# vswr.net
KiCad netlist of a schematic drawn in EAGLE
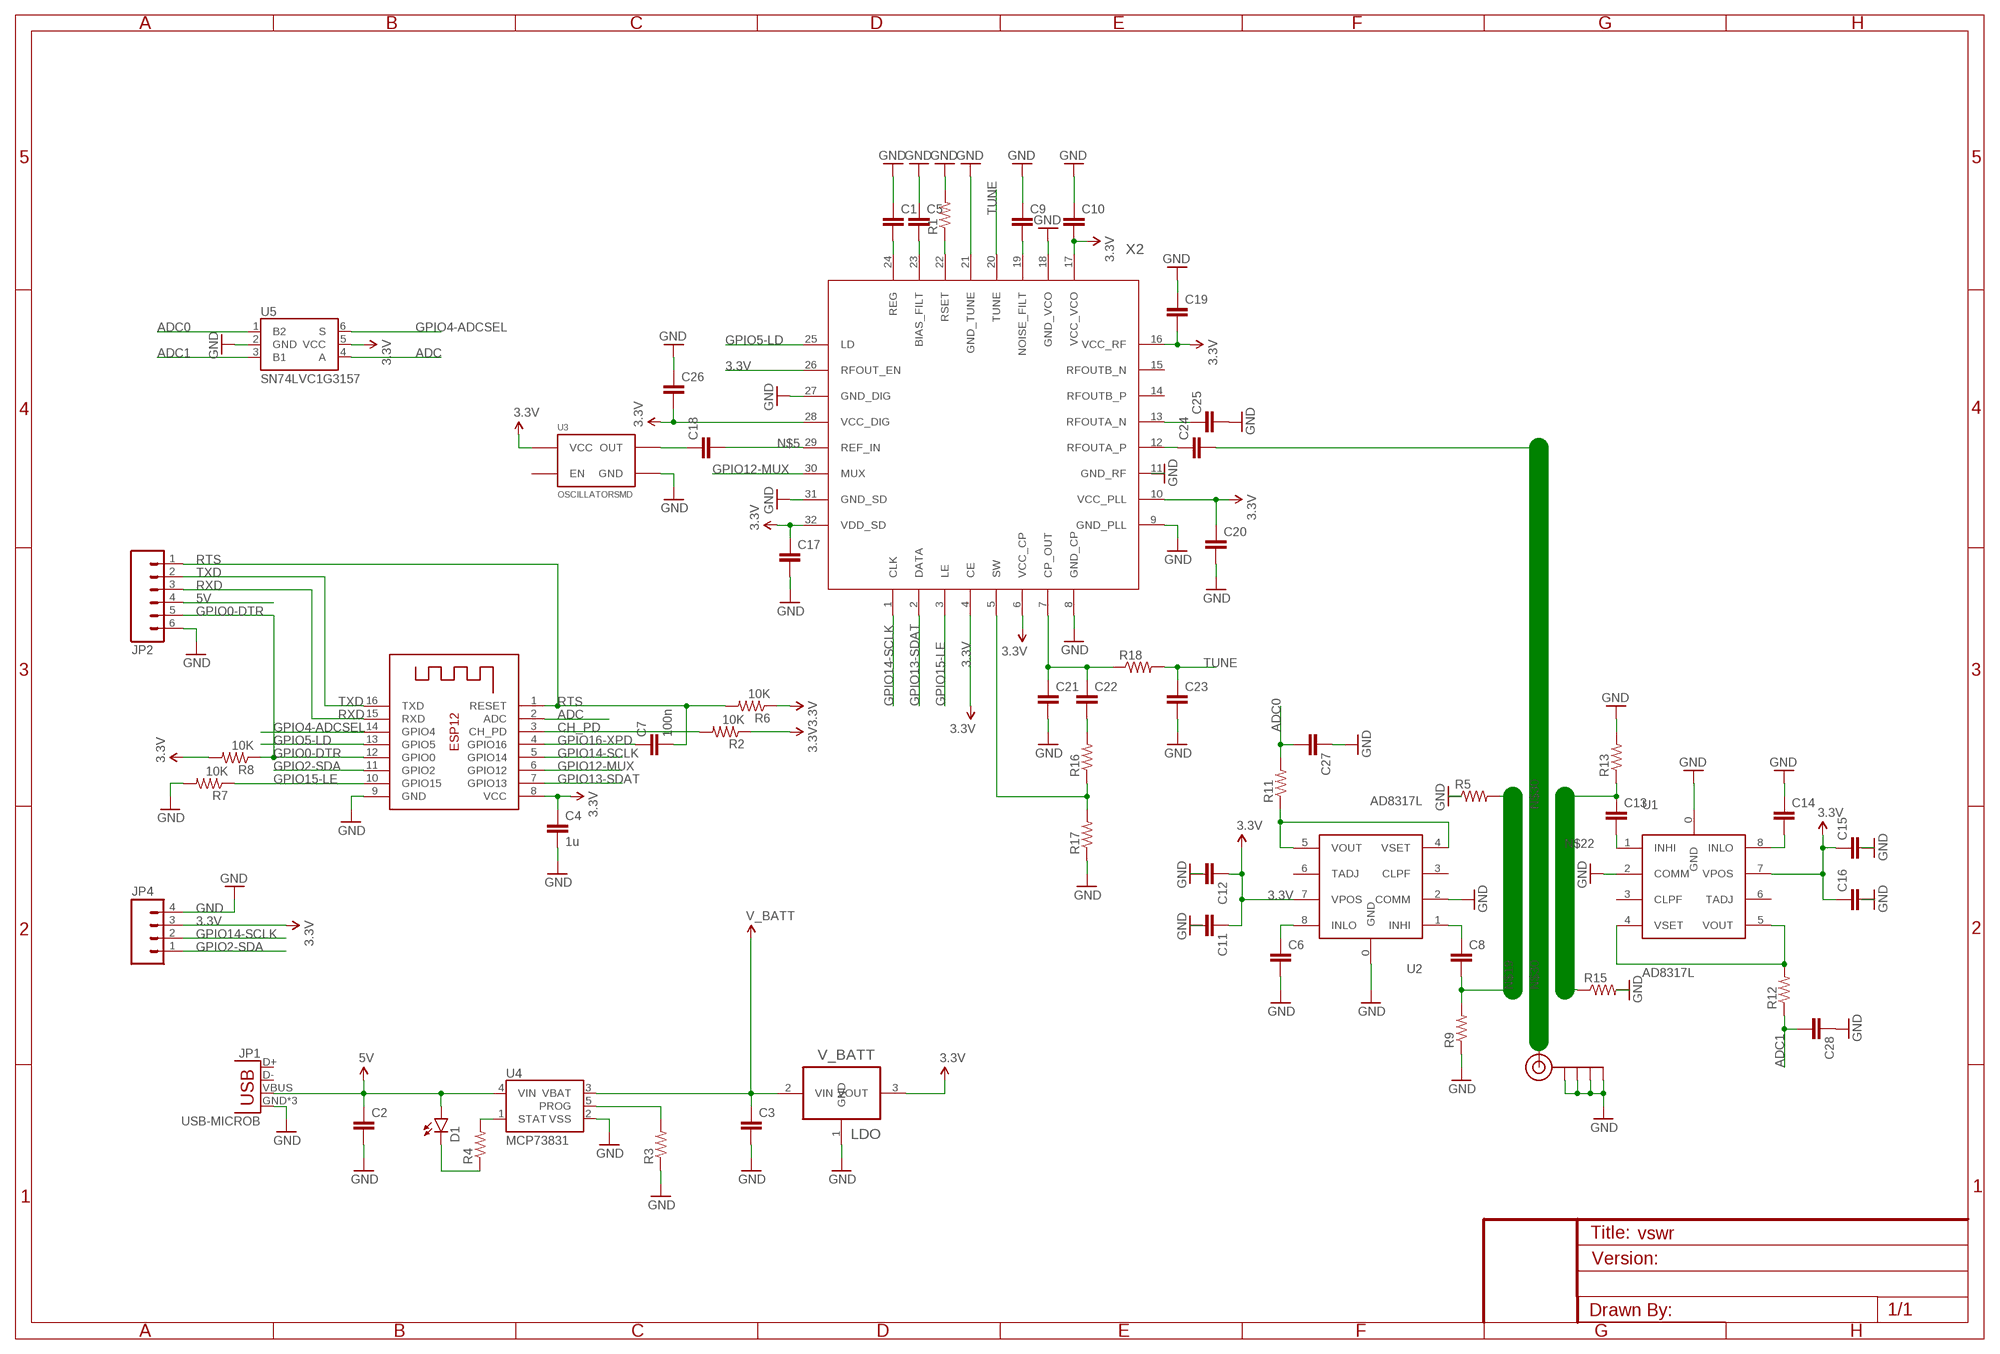
[diagram p0: schematic, sheet 1]

(export (version "E")
  (design (tool "Eeschema 10.0.6"))
  (components
    (comp (ref "C1")
      (value "CAP0402")
      (footprint "eagle-import:0402")
      (libsource (lib "eagle-import") (part "CAP0402"))
    )
    (comp (ref "C2")
      (value "CAP0603")
      (footprint "eagle-import:0603")
      (libsource (lib "eagle-import") (part "CAP0603"))
    )
    (comp (ref "C3")
      (value "CAP0603")
      (footprint "eagle-import:0603")
      (libsource (lib "eagle-import") (part "CAP0603"))
    )
    (comp (ref "C4")
      (value "1u")
      (footprint "eagle-import:0603")
      (libsource (lib "eagle-import") (part "naut_CAP0603"))
    )
    (comp (ref "C5")
      (value "CAP0402")
      (footprint "eagle-import:0402")
      (libsource (lib "eagle-import") (part "CAP0402"))
    )
    (comp (ref "C6")
      (value "CAP0402")
      (footprint "eagle-import:0402")
      (libsource (lib "eagle-import") (part "CAP0402"))
    )
    (comp (ref "C7")
      (value "100n")
      (footprint "eagle-import:0603")
      (libsource (lib "eagle-import") (part "naut_CAP0603"))
    )
    (comp (ref "C8")
      (value "CAP0402")
      (footprint "eagle-import:0402")
      (libsource (lib "eagle-import") (part "CAP0402"))
    )
    (comp (ref "C9")
      (value "CAP0402")
      (footprint "eagle-import:0402")
      (libsource (lib "eagle-import") (part "CAP0402"))
    )
    (comp (ref "C10")
      (value "CAP0402")
      (footprint "eagle-import:0402")
      (libsource (lib "eagle-import") (part "CAP0402"))
    )
    (comp (ref "C11")
      (value "CAP0402")
      (footprint "eagle-import:0402")
      (libsource (lib "eagle-import") (part "CAP0402"))
    )
    (comp (ref "C12")
      (value "CAP0603")
      (footprint "eagle-import:0603")
      (libsource (lib "eagle-import") (part "CAP0603"))
    )
    (comp (ref "C13")
      (value "CAP0402")
      (footprint "eagle-import:0402")
      (libsource (lib "eagle-import") (part "CAP0402"))
    )
    (comp (ref "C14")
      (value "CAP0402")
      (footprint "eagle-import:0402")
      (libsource (lib "eagle-import") (part "CAP0402"))
    )
    (comp (ref "C15")
      (value "CAP0402")
      (footprint "eagle-import:0402")
      (libsource (lib "eagle-import") (part "CAP0402"))
    )
    (comp (ref "C16")
      (value "CAP0603")
      (footprint "eagle-import:0603")
      (libsource (lib "eagle-import") (part "CAP0603"))
    )
    (comp (ref "C17")
      (value "CAP0402")
      (footprint "eagle-import:0402")
      (libsource (lib "eagle-import") (part "CAP0402"))
    )
    (comp (ref "C18")
      (value "CAP0402")
      (footprint "eagle-import:0402")
      (libsource (lib "eagle-import") (part "CAP0402"))
    )
    (comp (ref "C19")
      (value "CAP0402")
      (footprint "eagle-import:0402")
      (libsource (lib "eagle-import") (part "CAP0402"))
    )
    (comp (ref "C20")
      (value "CAP0402")
      (footprint "eagle-import:0402")
      (libsource (lib "eagle-import") (part "CAP0402"))
    )
    (comp (ref "C21")
      (value "CAP0603")
      (footprint "eagle-import:0603")
      (libsource (lib "eagle-import") (part "CAP0603"))
    )
    (comp (ref "C22")
      (value "CAP0603")
      (footprint "eagle-import:0603")
      (libsource (lib "eagle-import") (part "CAP0603"))
    )
    (comp (ref "C23")
      (value "CAP0603")
      (footprint "eagle-import:0603")
      (libsource (lib "eagle-import") (part "CAP0603"))
    )
    (comp (ref "C24")
      (value "CAP0402")
      (footprint "eagle-import:0402")
      (libsource (lib "eagle-import") (part "CAP0402"))
    )
    (comp (ref "C25")
      (value "CAP0402")
      (footprint "eagle-import:0402")
      (libsource (lib "eagle-import") (part "CAP0402"))
    )
    (comp (ref "C26")
      (value "CAP0402")
      (footprint "eagle-import:0402")
      (libsource (lib "eagle-import") (part "CAP0402"))
    )
    (comp (ref "C27")
      (value "CAP0603")
      (footprint "eagle-import:0603")
      (libsource (lib "eagle-import") (part "CAP0603"))
    )
    (comp (ref "C28")
      (value "CAP0603")
      (footprint "eagle-import:0603")
      (libsource (lib "eagle-import") (part "CAP0603"))
    )
    (comp (ref "D1")
      (value "LED0603")
      (footprint "eagle-import:LED-0603")
      (libsource (lib "eagle-import") (part "LED0603"))
    )
    (comp (ref "J$1")
      (value "SMA_EDGE")
      (footprint "eagle-import:SMA-EDGE")
      (libsource (lib "eagle-import") (part "SMA_EDGE"))
    )
    (comp (ref "JP1")
      (value "USB-MICROB")
      (footprint "eagle-import:USB-MICROB")
      (libsource (lib "eagle-import") (part "USB-MICROB"))
    )
    (comp (ref "JP2")
      (value "M061X06-SMD_EDGE_FEMALE")
      (footprint "eagle-import:1X06-SMD_EDGE")
      (libsource (lib "eagle-import") (part "M061X06-SMD_EDGE_FEMALE"))
    )
    (comp (ref "JP4")
      (value "M04PTH")
      (footprint "eagle-import:1X04")
      (libsource (lib "eagle-import") (part "M04PTH"))
    )
    (comp (ref "R1")
      (value "RESISTOR0402")
      (footprint "eagle-import:0402")
      (libsource (lib "eagle-import") (part "RESISTOR0402"))
    )
    (comp (ref "R2")
      (value "10K")
      (footprint "eagle-import:0603")
      (libsource (lib "eagle-import") (part "RESISTOR0603"))
    )
    (comp (ref "R3")
      (value "RESISTOR0603")
      (footprint "eagle-import:0603")
      (libsource (lib "eagle-import") (part "naut_RESISTOR0603"))
    )
    (comp (ref "R4")
      (value "RESISTOR0603")
      (footprint "eagle-import:0603")
      (libsource (lib "eagle-import") (part "naut_RESISTOR0603"))
    )
    (comp (ref "R5")
      (value "RESISTOR0402")
      (footprint "eagle-import:0402")
      (libsource (lib "eagle-import") (part "RESISTOR0402"))
    )
    (comp (ref "R6")
      (value "10K")
      (footprint "eagle-import:0603")
      (libsource (lib "eagle-import") (part "RESISTOR0603"))
    )
    (comp (ref "R7")
      (value "10K")
      (footprint "eagle-import:0603")
      (libsource (lib "eagle-import") (part "RESISTOR0603"))
    )
    (comp (ref "R8")
      (value "10K")
      (footprint "eagle-import:0603")
      (libsource (lib "eagle-import") (part "RESISTOR0603"))
    )
    (comp (ref "R9")
      (value "RESISTOR0402")
      (footprint "eagle-import:0402")
      (libsource (lib "eagle-import") (part "RESISTOR0402"))
    )
    (comp (ref "R11")
      (value "RESISTOR0603")
      (footprint "eagle-import:0603")
      (libsource (lib "eagle-import") (part "RESISTOR0603"))
    )
    (comp (ref "R12")
      (value "RESISTOR0603")
      (footprint "eagle-import:0603")
      (libsource (lib "eagle-import") (part "RESISTOR0603"))
    )
    (comp (ref "R13")
      (value "RESISTOR0402")
      (footprint "eagle-import:0402")
      (libsource (lib "eagle-import") (part "RESISTOR0402"))
    )
    (comp (ref "R15")
      (value "RESISTOR0402")
      (footprint "eagle-import:0402")
      (libsource (lib "eagle-import") (part "RESISTOR0402"))
    )
    (comp (ref "R16")
      (value "RESISTOR0402")
      (footprint "eagle-import:0402")
      (libsource (lib "eagle-import") (part "RESISTOR0402"))
    )
    (comp (ref "R17")
      (value "RESISTOR0402")
      (footprint "eagle-import:0402")
      (libsource (lib "eagle-import") (part "RESISTOR0402"))
    )
    (comp (ref "R18")
      (value "RESISTOR0402")
      (footprint "eagle-import:0402")
      (libsource (lib "eagle-import") (part "RESISTOR0402"))
    )
    (comp (ref "U1")
      (value "AD8317L")
      (footprint "eagle-import:DFN-8-EXTRA")
      (libsource (lib "eagle-import") (part "AD8317L"))
    )
    (comp (ref "U2")
      (value "AD8317L")
      (footprint "eagle-import:DFN-8-EXTRA")
      (libsource (lib "eagle-import") (part "AD8317L"))
    )
    (comp (ref "U3")
      (value "OSCILLATORSMD")
      (footprint "eagle-import:CRYSTAL-SMD-7X5")
      (libsource (lib "eagle-import") (part "OSCILLATORSMD"))
    )
    (comp (ref "U4")
      (value "MCP73831")
      (footprint "eagle-import:SOT23-5")
      (libsource (lib "eagle-import") (part "MCP73831"))
    )
    (comp (ref "U5")
      (value "SN74LVC1G3157")
      (footprint "eagle-import:SOT23-6")
      (libsource (lib "eagle-import") (part "SN74LVC1G3157"))
    )
    (comp (ref "V_BATT")
      (value "LDO")
      (footprint "eagle-import:SOT89R")
      (libsource (lib "eagle-import") (part "MCP1700T-3302E/TTSOT89MCP1700-3N"))
    )
    (comp (ref "X1")
      (value "ESP-12")
      (footprint "eagle-import:ESP-12")
      (libsource (lib "eagle-import") (part "ESP-12"))
    )
    (comp (ref "X2")
      (value "MAX2870TQFN-32-EXTRA")
      (footprint "eagle-import:TQFN-32-EXTRA")
      (libsource (lib "eagle-import") (part "MAX2870TQFN-32-EXTRA"))
    )
  )
  (nets
    (net (code "1") (name "/ADC") (class "Default")
      (node (ref "U5") (pin "4") (pinfunction "A_4") (pintype "output"))
      (node (ref "X1") (pin "2") (pinfunction "ADC_2") (pintype "passive"))
    )
    (net (code "2") (name "/ADC0") (class "Default")
      (node (ref "C27") (pin "2") (pinfunction "2_2") (pintype "passive"))
      (node (ref "R11") (pin "2") (pinfunction "2_2") (pintype "passive"))
      (node (ref "U5") (pin "1") (pinfunction "B2_1") (pintype "input"))
    )
    (net (code "3") (name "/ADC1") (class "Default")
      (node (ref "C28") (pin "2") (pinfunction "2_2") (pintype "passive"))
      (node (ref "R12") (pin "1") (pinfunction "1_1") (pintype "passive"))
      (node (ref "U5") (pin "3") (pinfunction "B1_3") (pintype "input"))
    )
    (net (code "4") (name "/CH_PD") (class "Default")
      (node (ref "R2") (pin "2") (pinfunction "2_2") (pintype "passive"))
      (node (ref "X1") (pin "3") (pinfunction "CH_PD_3") (pintype "input"))
    )
    (net (code "5") (name "/GPIO0-DTR") (class "Default")
      (node (ref "JP2") (pin "5") (pinfunction "5_5") (pintype "passive"))
      (node (ref "R8") (pin "1") (pinfunction "1_1") (pintype "passive"))
      (node (ref "X1") (pin "12") (pinfunction "GPIO0_12") (pintype "bidirectional"))
    )
    (net (code "6") (name "/GPIO2-SDA") (class "Default")
      (node (ref "JP4") (pin "1") (pinfunction "1_1") (pintype "passive"))
      (node (ref "X1") (pin "11") (pinfunction "GPIO2_11") (pintype "bidirectional"))
    )
    (net (code "7") (name "/GPIO4-ADCSEL") (class "Default")
      (node (ref "U5") (pin "6") (pinfunction "S_6") (pintype "input"))
      (node (ref "X1") (pin "14") (pinfunction "GPIO4_14") (pintype "bidirectional"))
    )
    (net (code "8") (name "/GPIO5-LD") (class "Default")
      (node (ref "X1") (pin "13") (pinfunction "GPIO5_13") (pintype "bidirectional"))
      (node (ref "X2") (pin "25") (pinfunction "LD_25") (pintype "bidirectional"))
    )
    (net (code "9") (name "/GPIO12-MUX") (class "Default")
      (node (ref "X1") (pin "6") (pinfunction "GPIO12_6") (pintype "bidirectional"))
      (node (ref "X2") (pin "30") (pinfunction "MUX_30") (pintype "bidirectional"))
    )
    (net (code "10") (name "/GPIO13-SDAT") (class "Default")
      (node (ref "X1") (pin "7") (pinfunction "GPIO13_7") (pintype "bidirectional"))
      (node (ref "X2") (pin "2") (pinfunction "DATA_2") (pintype "bidirectional"))
    )
    (net (code "11") (name "/GPIO14-SCLK") (class "Default")
      (node (ref "JP4") (pin "2") (pinfunction "2_2") (pintype "passive"))
      (node (ref "X1") (pin "5") (pinfunction "GPIO14_5") (pintype "bidirectional"))
      (node (ref "X2") (pin "1") (pinfunction "CLK_1") (pintype "bidirectional"))
    )
    (net (code "12") (name "/GPIO15-LE") (class "Default")
      (node (ref "R7") (pin "1") (pinfunction "1_1") (pintype "passive"))
      (node (ref "X1") (pin "10") (pinfunction "GPIO15_10") (pintype "bidirectional"))
      (node (ref "X2") (pin "3") (pinfunction "LE_3") (pintype "bidirectional"))
    )
    (net (code "13") (name "/GPIO16-XPD") (class "Default")
      (node (ref "C7") (pin "1") (pinfunction "1_1") (pintype "passive"))
      (node (ref "X1") (pin "4") (pinfunction "GPIO16_4") (pintype "bidirectional"))
    )
    (net (code "14") (name "/N$5") (class "Default")
      (node (ref "C18") (pin "2") (pinfunction "2_2") (pintype "passive"))
      (node (ref "X2") (pin "29") (pinfunction "REF_IN_29") (pintype "bidirectional"))
    )
    (net (code "15") (name "/N$19") (class "Default")
      (node (ref "C8") (pin "2") (pinfunction "2_2") (pintype "passive"))
      (node (ref "R5") (pin "2") (pinfunction "2_2") (pintype "passive"))
      (node (ref "R9") (pin "2") (pinfunction "2_2") (pintype "passive"))
    )
    (net (code "16") (name "/N$22") (class "Default")
      (node (ref "C13") (pin "1") (pinfunction "1_1") (pintype "passive"))
      (node (ref "R13") (pin "1") (pinfunction "1_1") (pintype "passive"))
      (node (ref "R15") (pin "1") (pinfunction "1_1") (pintype "passive"))
    )
    (net (code "17") (name "/N$30") (class "Default")
      (node (ref "C24") (pin "2") (pinfunction "2_2") (pintype "passive"))
      (node (ref "J$1") (pin "SIG") (pinfunction "SIGNAL_SIG") (pintype "bidirectional"))
    )
    (net (code "18") (name "/RTS") (class "Default")
      (node (ref "C7") (pin "2") (pinfunction "2_2") (pintype "passive"))
      (node (ref "JP2") (pin "1") (pinfunction "1_1") (pintype "passive"))
      (node (ref "R6") (pin "2") (pinfunction "2_2") (pintype "passive"))
      (node (ref "X1") (pin "1") (pinfunction "RESET_1") (pintype "input"))
    )
    (net (code "19") (name "/RXD") (class "Default")
      (node (ref "JP2") (pin "3") (pinfunction "3_3") (pintype "passive"))
      (node (ref "X1") (pin "15") (pinfunction "RXD_15") (pintype "input"))
    )
    (net (code "20") (name "/TUNE") (class "Default")
      (node (ref "C23") (pin "1") (pinfunction "1_1") (pintype "passive"))
      (node (ref "R18") (pin "2") (pinfunction "2_2") (pintype "passive"))
      (node (ref "X2") (pin "20") (pinfunction "TUNE_20") (pintype "passive"))
    )
    (net (code "21") (name "/TXD") (class "Default")
      (node (ref "JP2") (pin "2") (pinfunction "2_2") (pintype "passive"))
      (node (ref "X1") (pin "16") (pinfunction "TXD_16") (pintype "output"))
    )
    (net (code "22") (name "3.3V") (class "Default")
      (node (ref "C10") (pin "2") (pinfunction "2_2") (pintype "passive"))
      (node (ref "C11") (pin "1") (pinfunction "1_1") (pintype "passive"))
      (node (ref "C12") (pin "1") (pinfunction "1_1") (pintype "passive"))
      (node (ref "C15") (pin "1") (pinfunction "1_1") (pintype "passive"))
      (node (ref "C16") (pin "1") (pinfunction "1_1") (pintype "passive"))
      (node (ref "C17") (pin "1") (pinfunction "1_1") (pintype "passive"))
      (node (ref "C19") (pin "2") (pinfunction "2_2") (pintype "passive"))
      (node (ref "C20") (pin "1") (pinfunction "1_1") (pintype "passive"))
      (node (ref "C26") (pin "2") (pinfunction "2_2") (pintype "passive"))
      (node (ref "C4") (pin "1") (pinfunction "1_1") (pintype "passive"))
      (node (ref "JP4") (pin "3") (pinfunction "3_3") (pintype "passive"))
      (node (ref "R2") (pin "1") (pinfunction "1_1") (pintype "passive"))
      (node (ref "R6") (pin "1") (pinfunction "1_1") (pintype "passive"))
      (node (ref "R8") (pin "2") (pinfunction "2_2") (pintype "passive"))
      (node (ref "U1") (pin "7") (pinfunction "VPOS_7") (pintype "bidirectional"))
      (node (ref "U2") (pin "7") (pinfunction "VPOS_7") (pintype "bidirectional"))
      (node (ref "U3") (pin "P$4") (pinfunction "VCC_P$4") (pintype "bidirectional"))
      (node (ref "U5") (pin "5") (pinfunction "VCC_5") (pintype "power_in"))
      (node (ref "V_BATT") (pin "3") (pinfunction "VOUT_3") (pintype "output"))
      (node (ref "X1") (pin "8") (pinfunction "VCC_8") (pintype "power_in"))
      (node (ref "X2") (pin "10") (pinfunction "VCC_PLL_10") (pintype "power_in"))
      (node (ref "X2") (pin "16") (pinfunction "VCC_RF_16") (pintype "power_in"))
      (node (ref "X2") (pin "17") (pinfunction "VCC_VCO_17") (pintype "power_in"))
      (node (ref "X2") (pin "26") (pinfunction "RFOUT_EN_26") (pintype "bidirectional"))
      (node (ref "X2") (pin "28") (pinfunction "VCC_DIG_28") (pintype "power_in"))
      (node (ref "X2") (pin "32") (pinfunction "VDD_SD_32") (pintype "power_in"))
      (node (ref "X2") (pin "4") (pinfunction "CE_4") (pintype "power_in"))
      (node (ref "X2") (pin "6") (pinfunction "VCC_CP_6") (pintype "power_in"))
    )
    (net (code "23") (name "5V") (class "Default")
      (node (ref "C2") (pin "1") (pinfunction "1_1") (pintype "passive"))
      (node (ref "D1") (pin "A") (pinfunction "A_A") (pintype "passive"))
      (node (ref "JP1") (pin "VBUS") (pinfunction "VBUS_VBUS") (pintype "bidirectional"))
      (node (ref "JP2") (pin "4") (pinfunction "4_4") (pintype "passive"))
      (node (ref "U4") (pin "4") (pinfunction "VIN_4") (pintype "power_in"))
    )
    (net (code "24") (name "GND") (class "Default")
      (node (ref "C1") (pin "1") (pinfunction "1_1") (pintype "passive"))
      (node (ref "C10") (pin "1") (pinfunction "1_1") (pintype "passive"))
      (node (ref "C11") (pin "2") (pinfunction "2_2") (pintype "passive"))
      (node (ref "C12") (pin "2") (pinfunction "2_2") (pintype "passive"))
      (node (ref "C14") (pin "1") (pinfunction "1_1") (pintype "passive"))
      (node (ref "C15") (pin "2") (pinfunction "2_2") (pintype "passive"))
      (node (ref "C16") (pin "2") (pinfunction "2_2") (pintype "passive"))
      (node (ref "C17") (pin "2") (pinfunction "2_2") (pintype "passive"))
      (node (ref "C19") (pin "1") (pinfunction "1_1") (pintype "passive"))
      (node (ref "C2") (pin "2") (pinfunction "2_2") (pintype "passive"))
      (node (ref "C20") (pin "2") (pinfunction "2_2") (pintype "passive"))
      (node (ref "C21") (pin "2") (pinfunction "2_2") (pintype "passive"))
      (node (ref "C23") (pin "2") (pinfunction "2_2") (pintype "passive"))
      (node (ref "C25") (pin "2") (pinfunction "2_2") (pintype "passive"))
      (node (ref "C26") (pin "1") (pinfunction "1_1") (pintype "passive"))
      (node (ref "C27") (pin "1") (pinfunction "1_1") (pintype "passive"))
      (node (ref "C28") (pin "1") (pinfunction "1_1") (pintype "passive"))
      (node (ref "C3") (pin "2") (pinfunction "2_2") (pintype "passive"))
      (node (ref "C4") (pin "2") (pinfunction "2_2") (pintype "passive"))
      (node (ref "C5") (pin "1") (pinfunction "1_1") (pintype "passive"))
      (node (ref "C6") (pin "2") (pinfunction "2_2") (pintype "passive"))
      (node (ref "C9") (pin "1") (pinfunction "1_1") (pintype "passive"))
      (node (ref "J$1") (pin "GND@0") (pinfunction "GND_GND@0") (pintype "bidirectional"))
      (node (ref "J$1") (pin "GND@1") (pinfunction "GND_GND@1") (pintype "bidirectional"))
      (node (ref "J$1") (pin "GND@2") (pinfunction "GND_GND@2") (pintype "bidirectional"))
      (node (ref "J$1") (pin "GND@3") (pinfunction "GND_GND@3") (pintype "bidirectional"))
      (node (ref "JP1") (pin "GND") (pinfunction "GND_GND") (pintype "bidirectional"))
      (node (ref "JP1") (pin "MT1") (pinfunction "GND_MT1") (pintype "bidirectional"))
      (node (ref "JP1") (pin "MT2") (pinfunction "GND_MT2") (pintype "bidirectional"))
      (node (ref "JP2") (pin "6") (pinfunction "6_6") (pintype "passive"))
      (node (ref "JP4") (pin "4") (pinfunction "4_4") (pintype "passive"))
      (node (ref "R1") (pin "2") (pinfunction "2_2") (pintype "passive"))
      (node (ref "R13") (pin "2") (pinfunction "2_2") (pintype "passive"))
      (node (ref "R15") (pin "2") (pinfunction "2_2") (pintype "passive"))
      (node (ref "R17") (pin "1") (pinfunction "1_1") (pintype "passive"))
      (node (ref "R3") (pin "1") (pinfunction "1_1") (pintype "passive"))
      (node (ref "R5") (pin "1") (pinfunction "1_1") (pintype "passive"))
      (node (ref "R7") (pin "2") (pinfunction "2_2") (pintype "passive"))
      (node (ref "R9") (pin "1") (pinfunction "1_1") (pintype "passive"))
      (node (ref "U1") (pin "0") (pinfunction "GND_0") (pintype "bidirectional"))
      (node (ref "U1") (pin "2") (pinfunction "COMM_2") (pintype "bidirectional"))
      (node (ref "U2") (pin "0") (pinfunction "GND_0") (pintype "bidirectional"))
      (node (ref "U2") (pin "2") (pinfunction "COMM_2") (pintype "bidirectional"))
      (node (ref "U3") (pin "P$2") (pinfunction "GND_P$2") (pintype "bidirectional"))
      (node (ref "U4") (pin "2") (pinfunction "VSS_2") (pintype "power_in"))
      (node (ref "U5") (pin "2") (pinfunction "GND_2") (pintype "power_in"))
      (node (ref "V_BATT") (pin "1") (pinfunction "GND_1") (pintype "passive"))
      (node (ref "X1") (pin "9") (pinfunction "GND_9") (pintype "power_in"))
      (node (ref "X2") (pin "11") (pinfunction "GND_RF_11") (pintype "power_in"))
      (node (ref "X2") (pin "18") (pinfunction "GND_VCO_18") (pintype "power_in"))
      (node (ref "X2") (pin "21") (pinfunction "GND_TUNE_21") (pintype "power_in"))
      (node (ref "X2") (pin "27") (pinfunction "GND_DIG_27") (pintype "power_in"))
      (node (ref "X2") (pin "31") (pinfunction "GND_SD_31") (pintype "power_in"))
      (node (ref "X2") (pin "8") (pinfunction "GND_CP_8") (pintype "power_in"))
      (node (ref "X2") (pin "9") (pinfunction "GND_PLL_9") (pintype "power_in"))
    )
    (net (code "25") (name "Net-(C22-Pad2)") (class "Default")
      (node (ref "C22") (pin "2") (pinfunction "2_2") (pintype "passive"))
      (node (ref "R16") (pin "2") (pinfunction "2_2") (pintype "passive"))
    )
    (net (code "26") (name "Net-(D1-PadC)") (class "Default")
      (node (ref "D1") (pin "C") (pinfunction "C_C") (pintype "passive"))
      (node (ref "R4") (pin "1") (pinfunction "1_1") (pintype "passive"))
    )
    (net (code "27") (name "Net-(U1-INHI)") (class "Default")
      (node (ref "C13") (pin "2") (pinfunction "2_2") (pintype "passive"))
      (node (ref "U1") (pin "1") (pinfunction "INHI_1") (pintype "bidirectional"))
    )
    (net (code "28") (name "Net-(U1-INLO)") (class "Default")
      (node (ref "C14") (pin "2") (pinfunction "2_2") (pintype "passive"))
      (node (ref "U1") (pin "8") (pinfunction "INLO_8") (pintype "bidirectional"))
    )
    (net (code "29") (name "Net-(U1-VOUT)") (class "Default")
      (node (ref "R12") (pin "2") (pinfunction "2_2") (pintype "passive"))
      (node (ref "U1") (pin "4") (pinfunction "VSET_4") (pintype "bidirectional"))
      (node (ref "U1") (pin "5") (pinfunction "VOUT_5") (pintype "bidirectional"))
    )
    (net (code "30") (name "Net-(U2-INHI)") (class "Default")
      (node (ref "C8") (pin "1") (pinfunction "1_1") (pintype "passive"))
      (node (ref "U2") (pin "1") (pinfunction "INHI_1") (pintype "bidirectional"))
    )
    (net (code "31") (name "Net-(U2-INLO)") (class "Default")
      (node (ref "C6") (pin "1") (pinfunction "1_1") (pintype "passive"))
      (node (ref "U2") (pin "8") (pinfunction "INLO_8") (pintype "bidirectional"))
    )
    (net (code "32") (name "Net-(U2-VOUT)") (class "Default")
      (node (ref "R11") (pin "1") (pinfunction "1_1") (pintype "passive"))
      (node (ref "U2") (pin "4") (pinfunction "VSET_4") (pintype "bidirectional"))
      (node (ref "U2") (pin "5") (pinfunction "VOUT_5") (pintype "bidirectional"))
    )
    (net (code "33") (name "Net-(U3-OUT)") (class "Default")
      (node (ref "C18") (pin "1") (pinfunction "1_1") (pintype "passive"))
      (node (ref "U3") (pin "P$3") (pinfunction "OUT_P$3") (pintype "bidirectional"))
    )
    (net (code "34") (name "Net-(U4-PROG)") (class "Default")
      (node (ref "R3") (pin "2") (pinfunction "2_2") (pintype "passive"))
      (node (ref "U4") (pin "5") (pinfunction "PROG_5") (pintype "input"))
    )
    (net (code "35") (name "Net-(U4-STAT)") (class "Default")
      (node (ref "R4") (pin "2") (pinfunction "2_2") (pintype "passive"))
      (node (ref "U4") (pin "1") (pinfunction "STAT_1") (pintype "output"))
    )
    (net (code "36") (name "Net-(X2-BIAS_FILT)") (class "Default")
      (node (ref "C5") (pin "2") (pinfunction "2_2") (pintype "passive"))
      (node (ref "X2") (pin "23") (pinfunction "BIAS_FILT_23") (pintype "bidirectional"))
    )
    (net (code "37") (name "Net-(X2-CP_OUT)") (class "Default")
      (node (ref "C21") (pin "1") (pinfunction "1_1") (pintype "passive"))
      (node (ref "C22") (pin "1") (pinfunction "1_1") (pintype "passive"))
      (node (ref "R18") (pin "1") (pinfunction "1_1") (pintype "passive"))
      (node (ref "X2") (pin "7") (pinfunction "CP_OUT_7") (pintype "bidirectional"))
    )
    (net (code "38") (name "Net-(X2-NOISE_FILT)") (class "Default")
      (node (ref "C9") (pin "2") (pinfunction "2_2") (pintype "passive"))
      (node (ref "X2") (pin "19") (pinfunction "NOISE_FILT_19") (pintype "bidirectional"))
    )
    (net (code "39") (name "Net-(X2-REG)") (class "Default")
      (node (ref "C1") (pin "2") (pinfunction "2_2") (pintype "passive"))
      (node (ref "X2") (pin "24") (pinfunction "REG_24") (pintype "bidirectional"))
    )
    (net (code "40") (name "Net-(X2-RFOUTA_N)") (class "Default")
      (node (ref "C25") (pin "1") (pinfunction "1_1") (pintype "passive"))
      (node (ref "X2") (pin "13") (pinfunction "RFOUTA_N_13") (pintype "passive"))
    )
    (net (code "41") (name "Net-(X2-RFOUTA_P)") (class "Default")
      (node (ref "C24") (pin "1") (pinfunction "1_1") (pintype "passive"))
      (node (ref "X2") (pin "12") (pinfunction "RFOUTA_P_12") (pintype "power_in"))
    )
    (net (code "42") (name "Net-(X2-RSET)") (class "Default")
      (node (ref "R1") (pin "1") (pinfunction "1_1") (pintype "passive"))
      (node (ref "X2") (pin "22") (pinfunction "RSET_22") (pintype "bidirectional"))
    )
    (net (code "43") (name "Net-(X2-SW)") (class "Default")
      (node (ref "R16") (pin "1") (pinfunction "1_1") (pintype "passive"))
      (node (ref "R17") (pin "2") (pinfunction "2_2") (pintype "passive"))
      (node (ref "X2") (pin "5") (pinfunction "SW_5") (pintype "passive"))
    )
    (net (code "44") (name "V_BATT") (class "Default")
      (node (ref "C3") (pin "1") (pinfunction "1_1") (pintype "passive"))
      (node (ref "U4") (pin "3") (pinfunction "VBAT_3") (pintype "power_in"))
      (node (ref "V_BATT") (pin "2") (pinfunction "VIN_2") (pintype "input"))
    )
    (net (code "45") (name "unconnected-(JP1-PadD+)") (class "Default")
      (node (ref "JP1") (pin "D+") (pinfunction "D+_D+") (pintype "bidirectional"))
    )
    (net (code "46") (name "unconnected-(JP1-PadD-)") (class "Default")
      (node (ref "JP1") (pin "D-") (pinfunction "D-_D-") (pintype "bidirectional"))
    )
    (net (code "47") (name "unconnected-(U1-CLPF-Pad3)") (class "Default")
      (node (ref "U1") (pin "3") (pinfunction "CLPF_3") (pintype "bidirectional"))
    )
    (net (code "48") (name "unconnected-(U1-TADJ-Pad6)") (class "Default")
      (node (ref "U1") (pin "6") (pinfunction "TADJ_6") (pintype "bidirectional"))
    )
    (net (code "49") (name "unconnected-(U2-CLPF-Pad3)") (class "Default")
      (node (ref "U2") (pin "3") (pinfunction "CLPF_3") (pintype "bidirectional"))
    )
    (net (code "50") (name "unconnected-(U2-TADJ-Pad6)") (class "Default")
      (node (ref "U2") (pin "6") (pinfunction "TADJ_6") (pintype "bidirectional"))
    )
    (net (code "51") (name "unconnected-(U3-EN-PadP$1)") (class "Default")
      (node (ref "U3") (pin "P$1") (pinfunction "EN_P$1") (pintype "bidirectional"))
    )
    (net (code "52") (name "unconnected-(X2-RFOUTB_N-Pad15)") (class "Default")
      (node (ref "X2") (pin "15") (pinfunction "RFOUTB_N_15") (pintype "bidirectional"))
    )
    (net (code "53") (name "unconnected-(X2-RFOUTB_P-Pad14)") (class "Default")
      (node (ref "X2") (pin "14") (pinfunction "RFOUTB_P_14") (pintype "bidirectional"))
    )
  )
)
